# BeagleboneCape-RevC.net
KiCad netlist of a schematic drawn in EAGLE
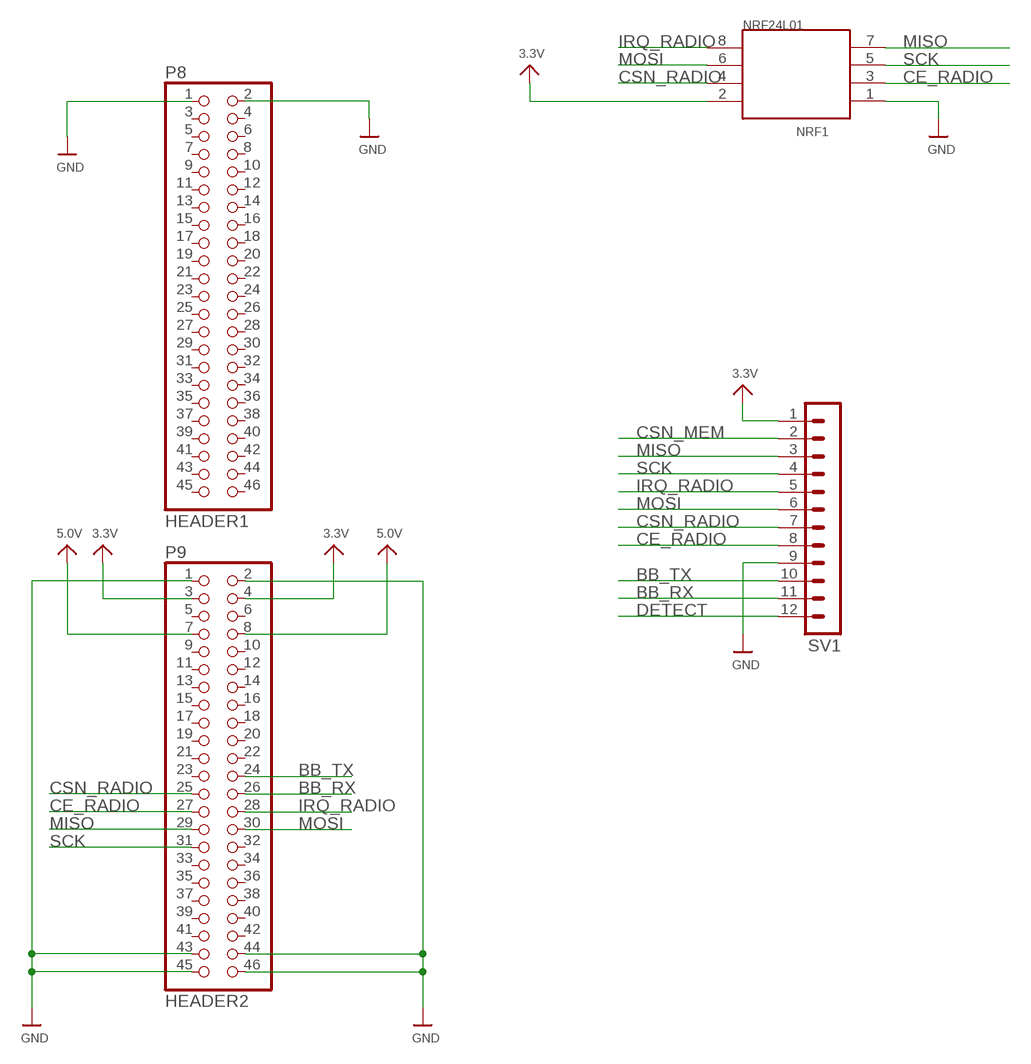
[diagram p0: schematic, sheet 1]

(export (version "E")
  (design (tool "Eeschema 10.0.6"))
  (components
    (comp (ref "NRF24L01")
      (value "NRF1")
      (footprint "eagle-import:TSM-110-XX-XXX-DV")
      (libsource (lib "eagle-import") (part "2X4SMDHEADER"))
    )
    (comp (ref "P8")
      (value "HEADER1")
      (footprint "eagle-import:2X23")
      (libsource (lib "eagle-import") (part "PINHD-2X24"))
    )
    (comp (ref "P9")
      (value "HEADER2")
      (footprint "eagle-import:2X23")
      (libsource (lib "eagle-import") (part "PINHD-2X24"))
    )
    (comp (ref "SV1")
      (value "MA12-1")
      (footprint "eagle-import:MA12-1")
      (libsource (lib "eagle-import") (part "MA12-1"))
    )
  )
  (nets
    (net (code "1") (name "/BB_RX") (class "Default")
      (node (ref "P9") (pin "26") (pinfunction "26_26") (pintype "passive"))
      (node (ref "SV1") (pin "11") (pinfunction "11_11") (pintype "passive"))
    )
    (net (code "2") (name "/BB_TX") (class "Default")
      (node (ref "P9") (pin "24") (pinfunction "24_24") (pintype "passive"))
      (node (ref "SV1") (pin "10") (pinfunction "10_10") (pintype "passive"))
    )
    (net (code "3") (name "/CE_RADIO") (class "Default")
      (node (ref "NRF24L01") (pin "3") (pinfunction "3_3") (pintype "bidirectional"))
      (node (ref "P9") (pin "27") (pinfunction "27_27") (pintype "passive"))
      (node (ref "SV1") (pin "8") (pinfunction "8_8") (pintype "passive"))
    )
    (net (code "4") (name "/CSN_MEM") (class "Default")
      (node (ref "SV1") (pin "2") (pinfunction "2_2") (pintype "passive"))
    )
    (net (code "5") (name "/CSN_RADIO") (class "Default")
      (node (ref "NRF24L01") (pin "4") (pinfunction "4_4") (pintype "bidirectional"))
      (node (ref "P9") (pin "25") (pinfunction "25_25") (pintype "passive"))
      (node (ref "SV1") (pin "7") (pinfunction "7_7") (pintype "passive"))
    )
    (net (code "6") (name "/DETECT") (class "Default")
      (node (ref "SV1") (pin "12") (pinfunction "12_12") (pintype "passive"))
    )
    (net (code "7") (name "/IRQ_RADIO") (class "Default")
      (node (ref "NRF24L01") (pin "8") (pinfunction "8_8") (pintype "bidirectional"))
      (node (ref "P9") (pin "28") (pinfunction "28_28") (pintype "passive"))
      (node (ref "SV1") (pin "5") (pinfunction "5_5") (pintype "passive"))
    )
    (net (code "8") (name "/MISO") (class "Default")
      (node (ref "NRF24L01") (pin "7") (pinfunction "7_7") (pintype "bidirectional"))
      (node (ref "P9") (pin "29") (pinfunction "29_29") (pintype "passive"))
      (node (ref "SV1") (pin "3") (pinfunction "3_3") (pintype "passive"))
    )
    (net (code "9") (name "/MOSI") (class "Default")
      (node (ref "NRF24L01") (pin "6") (pinfunction "6_6") (pintype "bidirectional"))
      (node (ref "P9") (pin "30") (pinfunction "30_30") (pintype "passive"))
      (node (ref "SV1") (pin "6") (pinfunction "6_6") (pintype "passive"))
    )
    (net (code "10") (name "/SCK") (class "Default")
      (node (ref "NRF24L01") (pin "5") (pinfunction "5_5") (pintype "bidirectional"))
      (node (ref "P9") (pin "31") (pinfunction "31_31") (pintype "passive"))
      (node (ref "SV1") (pin "4") (pinfunction "4_4") (pintype "passive"))
    )
    (net (code "11") (name "3.3V") (class "Default")
      (node (ref "NRF24L01") (pin "2") (pinfunction "2_2") (pintype "bidirectional"))
      (node (ref "P9") (pin "3") (pinfunction "3_3") (pintype "passive"))
      (node (ref "P9") (pin "4") (pinfunction "4_4") (pintype "passive"))
      (node (ref "SV1") (pin "1") (pinfunction "1_1") (pintype "passive"))
    )
    (net (code "12") (name "5.0V") (class "Default")
      (node (ref "P9") (pin "7") (pinfunction "7_7") (pintype "passive"))
      (node (ref "P9") (pin "8") (pinfunction "8_8") (pintype "passive"))
    )
    (net (code "13") (name "GND") (class "Default")
      (node (ref "NRF24L01") (pin "1") (pinfunction "1_1") (pintype "bidirectional"))
      (node (ref "P8") (pin "1") (pinfunction "1_1") (pintype "passive"))
      (node (ref "P8") (pin "2") (pinfunction "2_2") (pintype "passive"))
      (node (ref "P9") (pin "1") (pinfunction "1_1") (pintype "passive"))
      (node (ref "P9") (pin "2") (pinfunction "2_2") (pintype "passive"))
      (node (ref "P9") (pin "43") (pinfunction "43_43") (pintype "passive"))
      (node (ref "P9") (pin "44") (pinfunction "44_44") (pintype "passive"))
      (node (ref "P9") (pin "45") (pinfunction "45_45") (pintype "passive"))
      (node (ref "P9") (pin "46") (pinfunction "46_46") (pintype "passive"))
      (node (ref "SV1") (pin "9") (pinfunction "9_9") (pintype "passive"))
    )
    (net (code "14") (name "unconnected-(P8-Pad3)") (class "Default")
      (node (ref "P8") (pin "3") (pinfunction "3_3") (pintype "passive"))
    )
    (net (code "15") (name "unconnected-(P8-Pad4)") (class "Default")
      (node (ref "P8") (pin "4") (pinfunction "4_4") (pintype "passive"))
    )
    (net (code "16") (name "unconnected-(P8-Pad5)") (class "Default")
      (node (ref "P8") (pin "5") (pinfunction "5_5") (pintype "passive"))
    )
    (net (code "17") (name "unconnected-(P8-Pad6)") (class "Default")
      (node (ref "P8") (pin "6") (pinfunction "6_6") (pintype "passive"))
    )
    (net (code "18") (name "unconnected-(P8-Pad7)") (class "Default")
      (node (ref "P8") (pin "7") (pinfunction "7_7") (pintype "passive"))
    )
    (net (code "19") (name "unconnected-(P8-Pad8)") (class "Default")
      (node (ref "P8") (pin "8") (pinfunction "8_8") (pintype "passive"))
    )
    (net (code "20") (name "unconnected-(P8-Pad9)") (class "Default")
      (node (ref "P8") (pin "9") (pinfunction "9_9") (pintype "passive"))
    )
    (net (code "21") (name "unconnected-(P8-Pad10)") (class "Default")
      (node (ref "P8") (pin "10") (pinfunction "10_10") (pintype "passive"))
    )
    (net (code "22") (name "unconnected-(P8-Pad11)") (class "Default")
      (node (ref "P8") (pin "11") (pinfunction "11_11") (pintype "passive"))
    )
    (net (code "23") (name "unconnected-(P8-Pad12)") (class "Default")
      (node (ref "P8") (pin "12") (pinfunction "12_12") (pintype "passive"))
    )
    (net (code "24") (name "unconnected-(P8-Pad13)") (class "Default")
      (node (ref "P8") (pin "13") (pinfunction "13_13") (pintype "passive"))
    )
    (net (code "25") (name "unconnected-(P8-Pad14)") (class "Default")
      (node (ref "P8") (pin "14") (pinfunction "14_14") (pintype "passive"))
    )
    (net (code "26") (name "unconnected-(P8-Pad15)") (class "Default")
      (node (ref "P8") (pin "15") (pinfunction "15_15") (pintype "passive"))
    )
    (net (code "27") (name "unconnected-(P8-Pad16)") (class "Default")
      (node (ref "P8") (pin "16") (pinfunction "16_16") (pintype "passive"))
    )
    (net (code "28") (name "unconnected-(P8-Pad17)") (class "Default")
      (node (ref "P8") (pin "17") (pinfunction "17_17") (pintype "passive"))
    )
    (net (code "29") (name "unconnected-(P8-Pad18)") (class "Default")
      (node (ref "P8") (pin "18") (pinfunction "18_18") (pintype "passive"))
    )
    (net (code "30") (name "unconnected-(P8-Pad19)") (class "Default")
      (node (ref "P8") (pin "19") (pinfunction "19_19") (pintype "passive"))
    )
    (net (code "31") (name "unconnected-(P8-Pad20)") (class "Default")
      (node (ref "P8") (pin "20") (pinfunction "20_20") (pintype "passive"))
    )
    (net (code "32") (name "unconnected-(P8-Pad21)") (class "Default")
      (node (ref "P8") (pin "21") (pinfunction "21_21") (pintype "passive"))
    )
    (net (code "33") (name "unconnected-(P8-Pad22)") (class "Default")
      (node (ref "P8") (pin "22") (pinfunction "22_22") (pintype "passive"))
    )
    (net (code "34") (name "unconnected-(P8-Pad23)") (class "Default")
      (node (ref "P8") (pin "23") (pinfunction "23_23") (pintype "passive"))
    )
    (net (code "35") (name "unconnected-(P8-Pad24)") (class "Default")
      (node (ref "P8") (pin "24") (pinfunction "24_24") (pintype "passive"))
    )
    (net (code "36") (name "unconnected-(P8-Pad25)") (class "Default")
      (node (ref "P8") (pin "25") (pinfunction "25_25") (pintype "passive"))
    )
    (net (code "37") (name "unconnected-(P8-Pad26)") (class "Default")
      (node (ref "P8") (pin "26") (pinfunction "26_26") (pintype "passive"))
    )
    (net (code "38") (name "unconnected-(P8-Pad27)") (class "Default")
      (node (ref "P8") (pin "27") (pinfunction "27_27") (pintype "passive"))
    )
    (net (code "39") (name "unconnected-(P8-Pad28)") (class "Default")
      (node (ref "P8") (pin "28") (pinfunction "28_28") (pintype "passive"))
    )
    (net (code "40") (name "unconnected-(P8-Pad29)") (class "Default")
      (node (ref "P8") (pin "29") (pinfunction "29_29") (pintype "passive"))
    )
    (net (code "41") (name "unconnected-(P8-Pad30)") (class "Default")
      (node (ref "P8") (pin "30") (pinfunction "30_30") (pintype "passive"))
    )
    (net (code "42") (name "unconnected-(P8-Pad31)") (class "Default")
      (node (ref "P8") (pin "31") (pinfunction "31_31") (pintype "passive"))
    )
    (net (code "43") (name "unconnected-(P8-Pad32)") (class "Default")
      (node (ref "P8") (pin "32") (pinfunction "32_32") (pintype "passive"))
    )
    (net (code "44") (name "unconnected-(P8-Pad33)") (class "Default")
      (node (ref "P8") (pin "33") (pinfunction "33_33") (pintype "passive"))
    )
    (net (code "45") (name "unconnected-(P8-Pad34)") (class "Default")
      (node (ref "P8") (pin "34") (pinfunction "34_34") (pintype "passive"))
    )
    (net (code "46") (name "unconnected-(P8-Pad35)") (class "Default")
      (node (ref "P8") (pin "35") (pinfunction "35_35") (pintype "passive"))
    )
    (net (code "47") (name "unconnected-(P8-Pad36)") (class "Default")
      (node (ref "P8") (pin "36") (pinfunction "36_36") (pintype "passive"))
    )
    (net (code "48") (name "unconnected-(P8-Pad37)") (class "Default")
      (node (ref "P8") (pin "37") (pinfunction "37_37") (pintype "passive"))
    )
    (net (code "49") (name "unconnected-(P8-Pad38)") (class "Default")
      (node (ref "P8") (pin "38") (pinfunction "38_38") (pintype "passive"))
    )
    (net (code "50") (name "unconnected-(P8-Pad39)") (class "Default")
      (node (ref "P8") (pin "39") (pinfunction "39_39") (pintype "passive"))
    )
    (net (code "51") (name "unconnected-(P8-Pad40)") (class "Default")
      (node (ref "P8") (pin "40") (pinfunction "40_40") (pintype "passive"))
    )
    (net (code "52") (name "unconnected-(P8-Pad41)") (class "Default")
      (node (ref "P8") (pin "41") (pinfunction "41_41") (pintype "passive"))
    )
    (net (code "53") (name "unconnected-(P8-Pad42)") (class "Default")
      (node (ref "P8") (pin "42") (pinfunction "42_42") (pintype "passive"))
    )
    (net (code "54") (name "unconnected-(P8-Pad43)") (class "Default")
      (node (ref "P8") (pin "43") (pinfunction "43_43") (pintype "passive"))
    )
    (net (code "55") (name "unconnected-(P8-Pad44)") (class "Default")
      (node (ref "P8") (pin "44") (pinfunction "44_44") (pintype "passive"))
    )
    (net (code "56") (name "unconnected-(P8-Pad45)") (class "Default")
      (node (ref "P8") (pin "45") (pinfunction "45_45") (pintype "passive"))
    )
    (net (code "57") (name "unconnected-(P8-Pad46)") (class "Default")
      (node (ref "P8") (pin "46") (pinfunction "46_46") (pintype "passive"))
    )
    (net (code "58") (name "unconnected-(P9-Pad5)") (class "Default")
      (node (ref "P9") (pin "5") (pinfunction "5_5") (pintype "passive"))
    )
    (net (code "59") (name "unconnected-(P9-Pad6)") (class "Default")
      (node (ref "P9") (pin "6") (pinfunction "6_6") (pintype "passive"))
    )
    (net (code "60") (name "unconnected-(P9-Pad9)") (class "Default")
      (node (ref "P9") (pin "9") (pinfunction "9_9") (pintype "passive"))
    )
    (net (code "61") (name "unconnected-(P9-Pad10)") (class "Default")
      (node (ref "P9") (pin "10") (pinfunction "10_10") (pintype "passive"))
    )
    (net (code "62") (name "unconnected-(P9-Pad11)") (class "Default")
      (node (ref "P9") (pin "11") (pinfunction "11_11") (pintype "passive"))
    )
    (net (code "63") (name "unconnected-(P9-Pad12)") (class "Default")
      (node (ref "P9") (pin "12") (pinfunction "12_12") (pintype "passive"))
    )
    (net (code "64") (name "unconnected-(P9-Pad13)") (class "Default")
      (node (ref "P9") (pin "13") (pinfunction "13_13") (pintype "passive"))
    )
    (net (code "65") (name "unconnected-(P9-Pad14)") (class "Default")
      (node (ref "P9") (pin "14") (pinfunction "14_14") (pintype "passive"))
    )
    (net (code "66") (name "unconnected-(P9-Pad15)") (class "Default")
      (node (ref "P9") (pin "15") (pinfunction "15_15") (pintype "passive"))
    )
    (net (code "67") (name "unconnected-(P9-Pad16)") (class "Default")
      (node (ref "P9") (pin "16") (pinfunction "16_16") (pintype "passive"))
    )
    (net (code "68") (name "unconnected-(P9-Pad17)") (class "Default")
      (node (ref "P9") (pin "17") (pinfunction "17_17") (pintype "passive"))
    )
    (net (code "69") (name "unconnected-(P9-Pad18)") (class "Default")
      (node (ref "P9") (pin "18") (pinfunction "18_18") (pintype "passive"))
    )
    (net (code "70") (name "unconnected-(P9-Pad19)") (class "Default")
      (node (ref "P9") (pin "19") (pinfunction "19_19") (pintype "passive"))
    )
    (net (code "71") (name "unconnected-(P9-Pad20)") (class "Default")
      (node (ref "P9") (pin "20") (pinfunction "20_20") (pintype "passive"))
    )
    (net (code "72") (name "unconnected-(P9-Pad21)") (class "Default")
      (node (ref "P9") (pin "21") (pinfunction "21_21") (pintype "passive"))
    )
    (net (code "73") (name "unconnected-(P9-Pad22)") (class "Default")
      (node (ref "P9") (pin "22") (pinfunction "22_22") (pintype "passive"))
    )
    (net (code "74") (name "unconnected-(P9-Pad23)") (class "Default")
      (node (ref "P9") (pin "23") (pinfunction "23_23") (pintype "passive"))
    )
    (net (code "75") (name "unconnected-(P9-Pad32)") (class "Default")
      (node (ref "P9") (pin "32") (pinfunction "32_32") (pintype "passive"))
    )
    (net (code "76") (name "unconnected-(P9-Pad33)") (class "Default")
      (node (ref "P9") (pin "33") (pinfunction "33_33") (pintype "passive"))
    )
    (net (code "77") (name "unconnected-(P9-Pad34)") (class "Default")
      (node (ref "P9") (pin "34") (pinfunction "34_34") (pintype "passive"))
    )
    (net (code "78") (name "unconnected-(P9-Pad35)") (class "Default")
      (node (ref "P9") (pin "35") (pinfunction "35_35") (pintype "passive"))
    )
    (net (code "79") (name "unconnected-(P9-Pad36)") (class "Default")
      (node (ref "P9") (pin "36") (pinfunction "36_36") (pintype "passive"))
    )
    (net (code "80") (name "unconnected-(P9-Pad37)") (class "Default")
      (node (ref "P9") (pin "37") (pinfunction "37_37") (pintype "passive"))
    )
    (net (code "81") (name "unconnected-(P9-Pad38)") (class "Default")
      (node (ref "P9") (pin "38") (pinfunction "38_38") (pintype "passive"))
    )
    (net (code "82") (name "unconnected-(P9-Pad39)") (class "Default")
      (node (ref "P9") (pin "39") (pinfunction "39_39") (pintype "passive"))
    )
    (net (code "83") (name "unconnected-(P9-Pad40)") (class "Default")
      (node (ref "P9") (pin "40") (pinfunction "40_40") (pintype "passive"))
    )
    (net (code "84") (name "unconnected-(P9-Pad41)") (class "Default")
      (node (ref "P9") (pin "41") (pinfunction "41_41") (pintype "passive"))
    )
    (net (code "85") (name "unconnected-(P9-Pad42)") (class "Default")
      (node (ref "P9") (pin "42") (pinfunction "42_42") (pintype "passive"))
    )
  )
)
